# PM3_Bosclone_ANALOG_TX_4.net
KiCad netlist of a schematic drawn in Altium Designer
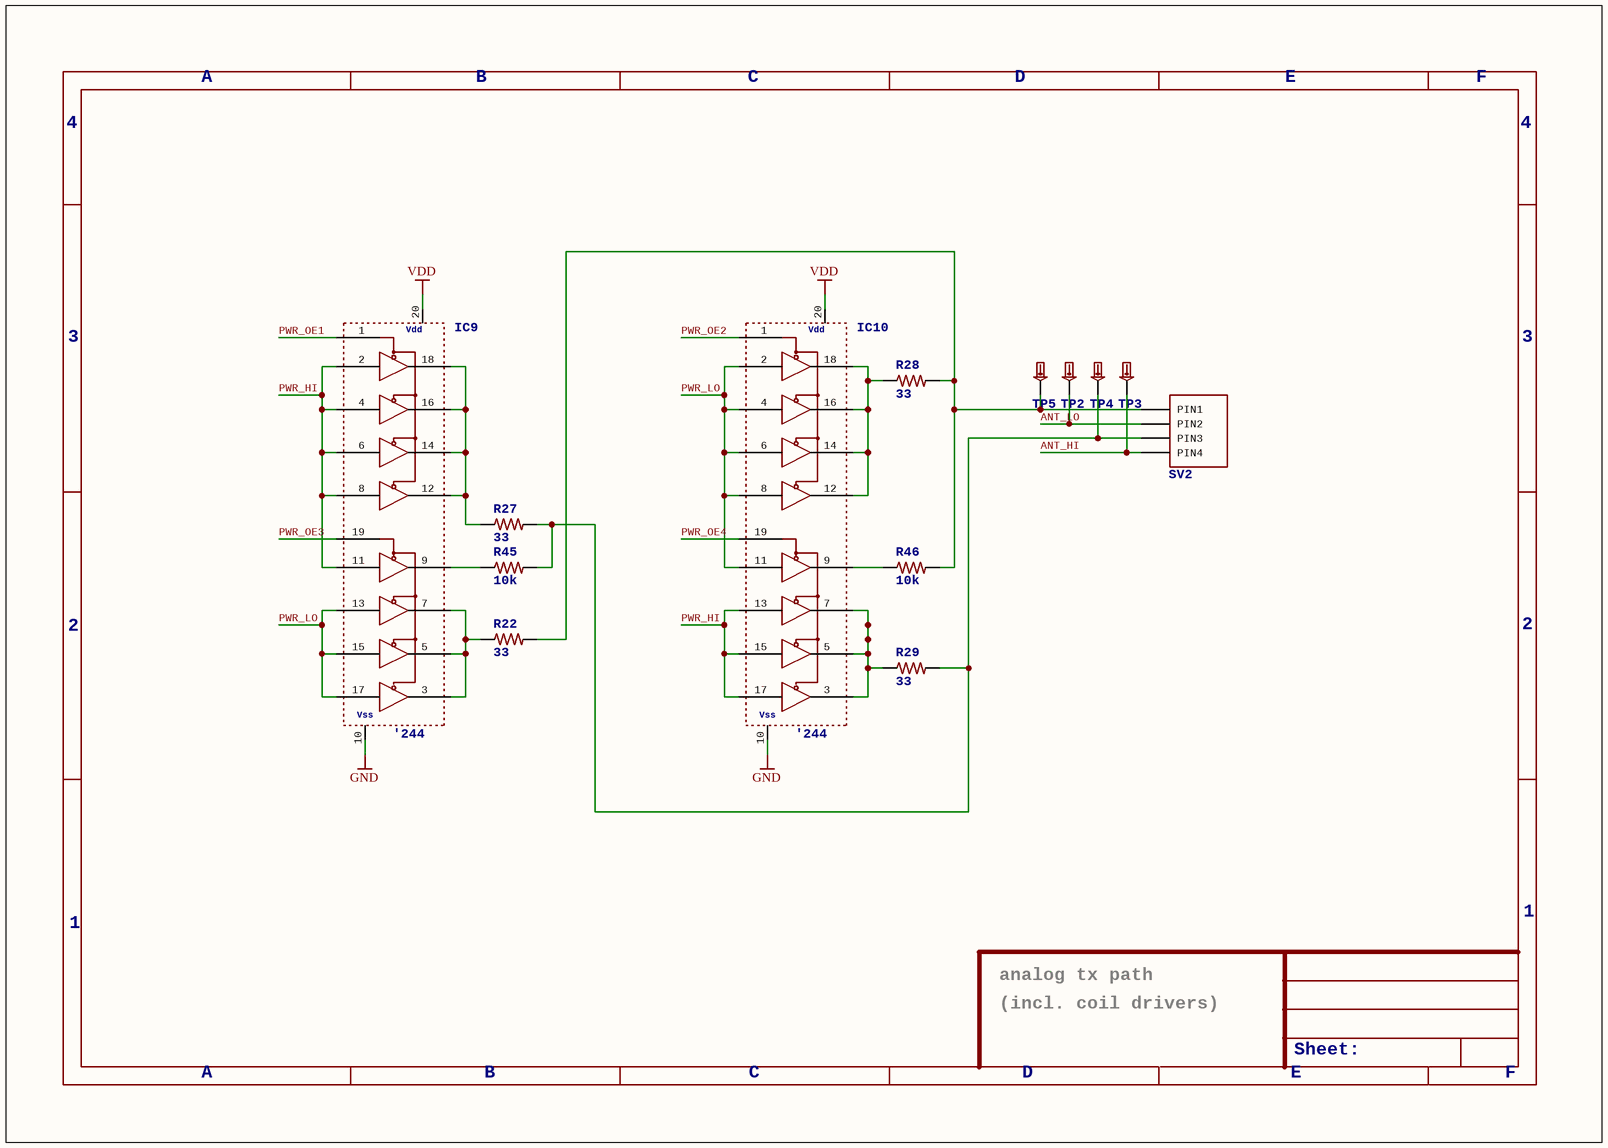
[diagram p0: PM3_Bosclone_ANALOG_TX_4.SchDoc]

(export (version "E")
  (design (tool "Eeschema 10.0.6"))
  (components
    (comp (ref "IC9")
      (value "74XX244-OCTAL-TRISTATE-BUFFERS")
      (footprint "TSSOP-20-extended")
      (fields (field (name "'244") "'244") (field (name "VDD") "Vdd") (field (name "VSS") "Vss"))
      (libsource (lib "merged") (part "74XX244-OCTAL-TRISTATE-BUFFERS"))
    )
    (comp (ref "IC10")
      (value "74XX244-OCTAL-TRISTATE-BUFFERS")
      (footprint "TSSOP-20-extended")
      (fields (field (name "'244") "'244") (field (name "VDD") "Vdd") (field (name "VSS") "Vss"))
      (libsource (lib "merged") (part "74XX244-OCTAL-TRISTATE-BUFFERS"))
    )
    (comp (ref "R22") (value "33") (footprint "RLC_0603") (libsource (lib "merged") (part "RESISTOR0603")))
    (comp (ref "R27") (value "33") (footprint "RLC_0603") (libsource (lib "merged") (part "RESISTOR0603")))
    (comp (ref "R28") (value "33") (footprint "RLC_0603") (libsource (lib "merged") (part "RESISTOR0603")))
    (comp (ref "R29") (value "33") (footprint "RLC_0603") (libsource (lib "merged") (part "RESISTOR0603")))
    (comp (ref "R45") (value "10k") (footprint "RLC_0603") (libsource (lib "merged") (part "RESISTOR0603")))
    (comp (ref "R46") (value "10k") (footprint "RLC_0603") (libsource (lib "merged") (part "RESISTOR0603")))
    (comp (ref "SV2")
      (value "HIROSE-MQ172-4POS")
      (footprint "HIROSE-MQ172-4POS")
      (libsource (lib "merged") (part "HIROSE-MQ172-4POS"))
    )
    (comp (ref "TP2")
      (value "TESTPADKEYSTONE-SMD")
      (footprint "KEYSTONE-SMD-TESTPOINT-5015")
      (libsource (lib "merged") (part "TESTPADKEYSTONE-SMD"))
    )
    (comp (ref "TP3")
      (value "TESTPADKEYSTONE-SMD")
      (footprint "KEYSTONE-SMD-TESTPOINT-5015")
      (libsource (lib "merged") (part "TESTPADKEYSTONE-SMD"))
    )
    (comp (ref "TP4")
      (value "TESTPADKEYSTONE-SMD")
      (footprint "KEYSTONE-SMD-TESTPOINT-5015")
      (libsource (lib "merged") (part "TESTPADKEYSTONE-SMD"))
    )
    (comp (ref "TP5")
      (value "TESTPADKEYSTONE-SMD")
      (footprint "KEYSTONE-SMD-TESTPOINT-5015")
      (libsource (lib "merged") (part "TESTPADKEYSTONE-SMD"))
    )
  )
  (nets
    (net (code "1") (name "/ANT_HI") (class "Default")
      (node (ref "SV2") (pin "4") (pinfunction "PIN4_4") (pintype "passive"))
      (node (ref "TP3") (pin "1") (pinfunction "P$1_1") (pintype "passive"))
    )
    (net (code "2") (name "/ANT_LO") (class "Default")
      (node (ref "SV2") (pin "2") (pinfunction "PIN2_2") (pintype "passive"))
      (node (ref "TP2") (pin "1") (pinfunction "P$1_1") (pintype "passive"))
    )
    (net (code "3") (name "/PWR_HI") (class "Default")
      (node (ref "IC10") (pin "13") (pinfunction "2A2_13") (pintype "passive"))
      (node (ref "IC10") (pin "15") (pinfunction "2A3_15") (pintype "passive"))
      (node (ref "IC10") (pin "17") (pinfunction "2A4_17") (pintype "passive"))
      (node (ref "IC9") (pin "11") (pinfunction "2A1_11") (pintype "passive"))
      (node (ref "IC9") (pin "2") (pinfunction "1A1_2") (pintype "passive"))
      (node (ref "IC9") (pin "4") (pinfunction "1A2_4") (pintype "passive"))
      (node (ref "IC9") (pin "6") (pinfunction "1A3_6") (pintype "passive"))
      (node (ref "IC9") (pin "8") (pinfunction "1A4_8") (pintype "passive"))
    )
    (net (code "4") (name "/PWR_LO") (class "Default")
      (node (ref "IC10") (pin "11") (pinfunction "2A1_11") (pintype "passive"))
      (node (ref "IC10") (pin "2") (pinfunction "1A1_2") (pintype "passive"))
      (node (ref "IC10") (pin "4") (pinfunction "1A2_4") (pintype "passive"))
      (node (ref "IC10") (pin "6") (pinfunction "1A3_6") (pintype "passive"))
      (node (ref "IC10") (pin "8") (pinfunction "1A4_8") (pintype "passive"))
      (node (ref "IC9") (pin "13") (pinfunction "2A2_13") (pintype "passive"))
      (node (ref "IC9") (pin "15") (pinfunction "2A3_15") (pintype "passive"))
      (node (ref "IC9") (pin "17") (pinfunction "2A4_17") (pintype "passive"))
    )
    (net (code "5") (name "/PWR_OE1") (class "Default")
      (node (ref "IC9") (pin "1") (pinfunction "1NOE_1") (pintype "passive"))
    )
    (net (code "6") (name "/PWR_OE2") (class "Default")
      (node (ref "IC10") (pin "1") (pinfunction "1NOE_1") (pintype "passive"))
    )
    (net (code "7") (name "/PWR_OE3") (class "Default")
      (node (ref "IC9") (pin "19") (pinfunction "2NOE_19") (pintype "passive"))
    )
    (net (code "8") (name "/PWR_OE4") (class "Default")
      (node (ref "IC10") (pin "19") (pinfunction "2NOE_19") (pintype "passive"))
    )
    (net (code "9") (name "GND") (class "Default")
      (node (ref "IC10") (pin "10") (pinfunction "VSS_10") (pintype "passive"))
      (node (ref "IC9") (pin "10") (pinfunction "VSS_10") (pintype "passive"))
    )
    (net (code "10") (name "Net-(IC9-1Y1)") (class "Default")
      (node (ref "IC9") (pin "12") (pinfunction "1Y4_12") (pintype "passive"))
      (node (ref "IC9") (pin "14") (pinfunction "1Y3_14") (pintype "passive"))
      (node (ref "IC9") (pin "16") (pinfunction "1Y2_16") (pintype "passive"))
      (node (ref "IC9") (pin "18") (pinfunction "1Y1_18") (pintype "passive"))
      (node (ref "R27") (pin "1") (pinfunction "1_1") (pintype "passive"))
    )
    (net (code "11") (name "Net-(IC9-2Y1)") (class "Default")
      (node (ref "IC9") (pin "9") (pinfunction "2Y1_9") (pintype "passive"))
      (node (ref "R45") (pin "1") (pinfunction "1_1") (pintype "passive"))
    )
    (net (code "12") (name "Net-(IC9-2Y2)") (class "Default")
      (node (ref "IC9") (pin "3") (pinfunction "2Y4_3") (pintype "passive"))
      (node (ref "IC9") (pin "5") (pinfunction "2Y3_5") (pintype "passive"))
      (node (ref "IC9") (pin "7") (pinfunction "2Y2_7") (pintype "passive"))
      (node (ref "R22") (pin "1") (pinfunction "1_1") (pintype "passive"))
    )
    (net (code "13") (name "Net-(IC10-1Y1)") (class "Default")
      (node (ref "IC10") (pin "12") (pinfunction "1Y4_12") (pintype "passive"))
      (node (ref "IC10") (pin "14") (pinfunction "1Y3_14") (pintype "passive"))
      (node (ref "IC10") (pin "16") (pinfunction "1Y2_16") (pintype "passive"))
      (node (ref "IC10") (pin "18") (pinfunction "1Y1_18") (pintype "passive"))
      (node (ref "R28") (pin "1") (pinfunction "1_1") (pintype "passive"))
    )
    (net (code "14") (name "Net-(IC10-2Y1)") (class "Default")
      (node (ref "IC10") (pin "9") (pinfunction "2Y1_9") (pintype "passive"))
      (node (ref "R46") (pin "1") (pinfunction "1_1") (pintype "passive"))
    )
    (net (code "15") (name "Net-(IC10-2Y2)") (class "Default")
      (node (ref "IC10") (pin "3") (pinfunction "2Y4_3") (pintype "passive"))
      (node (ref "IC10") (pin "5") (pinfunction "2Y3_5") (pintype "passive"))
      (node (ref "IC10") (pin "7") (pinfunction "2Y2_7") (pintype "passive"))
      (node (ref "R29") (pin "1") (pinfunction "1_1") (pintype "passive"))
    )
    (net (code "16") (name "Net-(SV2-PIN1)") (class "Default")
      (node (ref "R22") (pin "2") (pinfunction "2_2") (pintype "passive"))
      (node (ref "R28") (pin "2") (pinfunction "2_2") (pintype "passive"))
      (node (ref "R46") (pin "2") (pinfunction "2_2") (pintype "passive"))
      (node (ref "SV2") (pin "1") (pinfunction "PIN1_1") (pintype "passive"))
      (node (ref "TP5") (pin "1") (pinfunction "P$1_1") (pintype "passive"))
    )
    (net (code "17") (name "Net-(SV2-PIN3)") (class "Default")
      (node (ref "R27") (pin "2") (pinfunction "2_2") (pintype "passive"))
      (node (ref "R29") (pin "2") (pinfunction "2_2") (pintype "passive"))
      (node (ref "R45") (pin "2") (pinfunction "2_2") (pintype "passive"))
      (node (ref "SV2") (pin "3") (pinfunction "PIN3_3") (pintype "passive"))
      (node (ref "TP4") (pin "1") (pinfunction "P$1_1") (pintype "passive"))
    )
    (net (code "18") (name "VDD") (class "Default")
      (node (ref "IC10") (pin "20") (pinfunction "VDD_20") (pintype "passive"))
      (node (ref "IC9") (pin "20") (pinfunction "VDD_20") (pintype "passive"))
    )
  )
)
